# -.net
KiCad netlist of a schematic drawn in Altium Designer
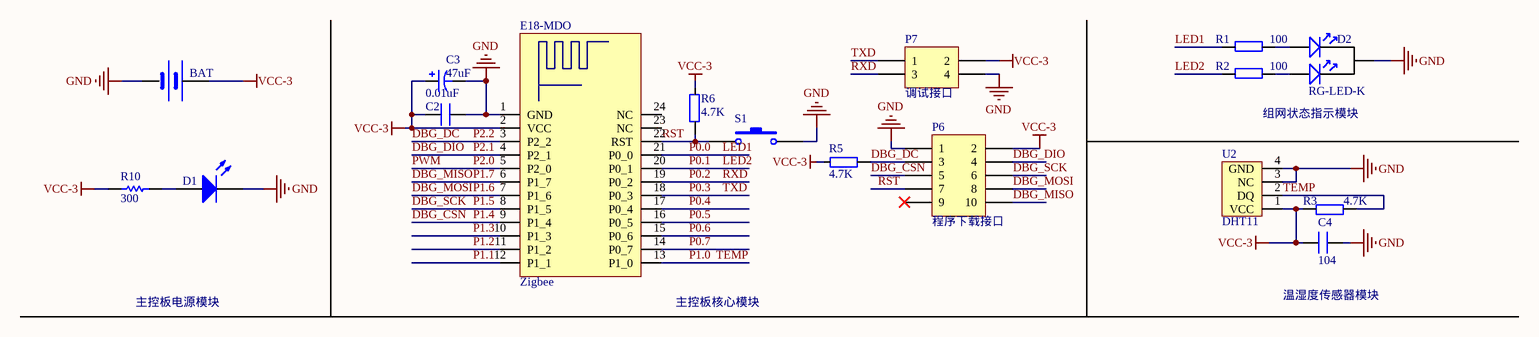
[diagram p0: 智能家居-温湿度传感器.SchDoc]

(export (version "E")
  (design (tool "Eeschema 10.0.6"))
  (components
    (comp (ref "BAT") (value "BATT") (footprint "BATM") (libsource (lib "WARSHIP") (part "BAT")))
    (comp (ref "C2") (value "0.01uF") (footprint "0.1UF") (libsource (lib "WARSHIP") (part "C")))
    (comp (ref "C3")
      (value "47uF")
      (footprint "CD5")
      (description "Polarized Capacitor (Radial)")
      (fields (field (name "Comment") "Cap Pol1") (field (name "PUBLISHER") "Altium Limited"))
      (libsource (lib "Miscellaneous Devices") (part "Cap Pol1"))
    )
    (comp (ref "C4") (value "104") (footprint "0.1UF") (libsource (lib "WARSHIP") (part "C")))
    (comp (ref "D1")
      (value "LED0")
      (footprint "LED-3")
      (description "Typical INFRARED GaAs LED")
      (fields (field (name "PUBLISHER") "Altium Limited"))
      (libsource (lib "Miscellaneous Devices") (part "LED0"))
    )
    (comp (ref "D2")
      (value "RG-LED-K")
      (footprint "RG-LED")
      (libsource (lib "ESP8266V1.2") (part "RG-LED-K"))
    )
    (comp (ref "E18-MDO")
      (value "Zigbee")
      (footprint "E18-MD0-1")
      (description "Zigbee模块")
      (libsource (lib "ESP8266V1.2") (part "E18-MDO"))
    )
    (comp (ref "P6")
      (value "程序下载接口")
      (footprint "HDR2X5")
      (description "Header, 5-Pin, Dual row")
      (fields (field (name "PUBLISHER") "Altium Limited"))
      (libsource (lib "Miscellaneous Connectors") (part "Header 5X2"))
    )
    (comp (ref "P7")
      (value "调试接口")
      (footprint "HDR2X2")
      (description "Header, 2-Pin, Dual row, Right Angle")
      (fields (field (name "PUBLISHER") "Altium Limited"))
      (libsource (lib "Miscellaneous Connectors") (part "Header 2X2H"))
    )
    (comp (ref "R1") (value "100") (footprint "AXIAL-0.3") (libsource (lib "ESP8266V1.2") (part "R")))
    (comp (ref "R2") (value "100") (footprint "AXIAL-0.3") (libsource (lib "ESP8266V1.2") (part "R")))
    (comp (ref "R3") (value "4.7K") (footprint "AXIAL-0.3") (libsource (lib "ESP8266V1.2") (part "R")))
    (comp (ref "R5") (value "4.7K") (footprint "AXIAL-0.3") (libsource (lib "ESP8266V1.2") (part "R")))
    (comp (ref "R6") (value "4.7K") (footprint "AXIAL-0.3") (libsource (lib "ESP8266V1.2") (part "R")))
    (comp (ref "R10")
      (value "300")
      (footprint "AXIAL-0.3")
      (description "Resistor")
      (fields (field (name "Comment") "Res1") (field (name "PUBLISHER") "Altium Limited"))
      (libsource (lib "Miscellaneous Devices") (part "Res1"))
    )
    (comp (ref "S1")
      (value "SW-PB")
      (footprint "KEY_M")
      (description "Switch")
      (fields (field (name "PUBLISHER") "Altium Limited"))
      (libsource (lib "Miscellaneous Devices") (part "SW-PB"))
    )
    (comp (ref "U2")
      (value "DHT11")
      (footprint "HDR1X4")
      (description "数字温湿度传感器")
      (libsource (lib "WARSHIP") (part "DHT11"))
    )
  )
  (nets
    (net (code "1") (name "/DBG_CSN") (class "Default")
      (node (ref "E18-MDO") (pin "9") (pinfunction "P1_4_9") (pintype "passive"))
      (node (ref "P6") (pin "5") (pinfunction "5_5") (pintype "passive"))
    )
    (net (code "2") (name "/DBG_DC") (class "Default")
      (node (ref "E18-MDO") (pin "3") (pinfunction "P2_2_3") (pintype "passive"))
      (node (ref "P6") (pin "3") (pinfunction "3_3") (pintype "passive"))
      (node (ref "R5") (pin "2") (pintype "passive"))
    )
    (net (code "3") (name "/DBG_DIO") (class "Default")
      (node (ref "E18-MDO") (pin "4") (pinfunction "P2_1_4") (pintype "passive"))
      (node (ref "P6") (pin "4") (pinfunction "4_4") (pintype "passive"))
    )
    (net (code "4") (name "/DBG_MISO") (class "Default")
      (node (ref "E18-MDO") (pin "6") (pinfunction "P1_7_6") (pintype "passive"))
      (node (ref "P6") (pin "10") (pinfunction "10_10") (pintype "passive"))
    )
    (net (code "5") (name "/DBG_MOSI") (class "Default")
      (node (ref "E18-MDO") (pin "7") (pinfunction "P1_6_7") (pintype "passive"))
      (node (ref "P6") (pin "8") (pinfunction "8_8") (pintype "passive"))
    )
    (net (code "6") (name "/DBG_SCK") (class "Default")
      (node (ref "E18-MDO") (pin "8") (pinfunction "P1_5_8") (pintype "passive"))
      (node (ref "P6") (pin "6") (pinfunction "6_6") (pintype "passive"))
    )
    (net (code "7") (name "/LED1") (class "Default")
      (node (ref "E18-MDO") (pin "21") (pinfunction "P0_0_21") (pintype "passive"))
      (node (ref "R1") (pin "2") (pintype "passive"))
    )
    (net (code "8") (name "/LED2") (class "Default")
      (node (ref "E18-MDO") (pin "20") (pinfunction "P0_1_20") (pintype "passive"))
      (node (ref "R2") (pin "2") (pintype "passive"))
    )
    (net (code "9") (name "/P0.2") (class "Default")
      (node (ref "E18-MDO") (pin "19") (pinfunction "P0_2_19") (pintype "passive"))
      (node (ref "P7") (pin "3") (pinfunction "3_3") (pintype "passive"))
    )
    (net (code "10") (name "/P0.3") (class "Default")
      (node (ref "E18-MDO") (pin "18") (pinfunction "P0_3_18") (pintype "passive"))
      (node (ref "P7") (pin "1") (pinfunction "1_1") (pintype "passive"))
    )
    (net (code "11") (name "/P0.4") (class "Default")
      (node (ref "E18-MDO") (pin "17") (pinfunction "P0_4_17") (pintype "passive"))
    )
    (net (code "12") (name "/P0.5") (class "Default")
      (node (ref "E18-MDO") (pin "16") (pinfunction "P0_5_16") (pintype "passive"))
    )
    (net (code "13") (name "/P0.6") (class "Default")
      (node (ref "E18-MDO") (pin "15") (pinfunction "P0_6_15") (pintype "passive"))
    )
    (net (code "14") (name "/P0.7") (class "Default")
      (node (ref "E18-MDO") (pin "14") (pinfunction "P0_7_14") (pintype "passive"))
    )
    (net (code "15") (name "/P1.0") (class "Default")
      (node (ref "E18-MDO") (pin "13") (pinfunction "P1_0_13") (pintype "passive"))
      (node (ref "R3") (pin "2") (pintype "passive"))
      (node (ref "U2") (pin "2") (pinfunction "DQ_2") (pintype "passive"))
    )
    (net (code "16") (name "/P1.1") (class "Default")
      (node (ref "E18-MDO") (pin "12") (pinfunction "P1_1_12") (pintype "passive"))
    )
    (net (code "17") (name "/P1.2") (class "Default")
      (node (ref "E18-MDO") (pin "11") (pinfunction "P1_2_11") (pintype "passive"))
    )
    (net (code "18") (name "/P1.3") (class "Default")
      (node (ref "E18-MDO") (pin "10") (pinfunction "P1_3_10") (pintype "passive"))
    )
    (net (code "19") (name "/P2.0") (class "Default")
      (node (ref "E18-MDO") (pin "5") (pinfunction "P2_0_5") (pintype "passive"))
    )
    (net (code "20") (name "/RST") (class "Default")
      (node (ref "E18-MDO") (pin "22") (pinfunction "RST_22") (pintype "passive"))
      (node (ref "P6") (pin "7") (pinfunction "7_7") (pintype "passive"))
      (node (ref "R6") (pin "2") (pintype "passive"))
      (node (ref "S1") (pin "1") (pinfunction "1_1") (pintype "passive"))
    )
    (net (code "21") (name "GND") (class "Default")
      (node (ref "BAT") (pin "2") (pinfunction "GND_2") (pintype "passive"))
      (node (ref "C2") (pin "2") (pintype "passive"))
      (node (ref "C3") (pin "2") (pinfunction "2_2") (pintype "passive"))
      (node (ref "C4") (pin "1") (pintype "passive"))
      (node (ref "D1") (pin "2") (pinfunction "K_2") (pintype "passive"))
      (node (ref "D2") (pin "2") (pinfunction "GND_2") (pintype "passive"))
      (node (ref "E18-MDO") (pin "1") (pinfunction "GND_1") (pintype "passive"))
      (node (ref "P6") (pin "1") (pinfunction "1_1") (pintype "passive"))
      (node (ref "P7") (pin "4") (pinfunction "4_4") (pintype "passive"))
      (node (ref "S1") (pin "2") (pinfunction "2_2") (pintype "passive"))
      (node (ref "U2") (pin "3") (pinfunction "NC_3") (pintype "passive"))
      (node (ref "U2") (pin "4") (pinfunction "GND_4") (pintype "passive"))
    )
    (net (code "22") (name "Net-(D1-A)") (class "Default")
      (node (ref "D1") (pin "1") (pinfunction "A_1") (pintype "passive"))
      (node (ref "R10") (pin "2") (pinfunction "2_2") (pintype "passive"))
    )
    (net (code "23") (name "Net-(D2-G)") (class "Default")
      (node (ref "D2") (pin "3") (pinfunction "G_3") (pintype "passive"))
      (node (ref "R2") (pin "1") (pintype "passive"))
    )
    (net (code "24") (name "Net-(D2-R)") (class "Default")
      (node (ref "D2") (pin "1") (pinfunction "R_1") (pintype "passive"))
      (node (ref "R1") (pin "1") (pintype "passive"))
    )
    (net (code "25") (name "VCC-3") (class "Default")
      (node (ref "BAT") (pin "1") (pinfunction "VCC_1") (pintype "passive"))
      (node (ref "C2") (pin "1") (pintype "passive"))
      (node (ref "C3") (pin "1") (pinfunction "1_1") (pintype "passive"))
      (node (ref "C4") (pin "2") (pintype "passive"))
      (node (ref "E18-MDO") (pin "2") (pinfunction "VCC_2") (pintype "passive"))
      (node (ref "P6") (pin "2") (pinfunction "2_2") (pintype "passive"))
      (node (ref "P7") (pin "2") (pinfunction "2_2") (pintype "passive"))
      (node (ref "R10") (pin "1") (pinfunction "1_1") (pintype "passive"))
      (node (ref "R3") (pin "1") (pintype "passive"))
      (node (ref "R5") (pin "1") (pintype "passive"))
      (node (ref "R6") (pin "1") (pintype "passive"))
      (node (ref "U2") (pin "1") (pinfunction "VCC_1") (pintype "passive"))
    )
    (net (code "26") (name "unconnected-(E18-MDO-NC-Pad23)") (class "Default")
      (node (ref "E18-MDO") (pin "23") (pinfunction "NC_23") (pintype "passive"))
    )
    (net (code "27") (name "unconnected-(E18-MDO-NC-Pad24)") (class "Default")
      (node (ref "E18-MDO") (pin "24") (pinfunction "NC_24") (pintype "passive"))
    )
    (net (code "28") (name "unconnected-(P6-Pad9)") (class "Default")
      (node (ref "P6") (pin "9") (pinfunction "9_9") (pintype "passive+no_connect"))
    )
  )
)
